# Lamp_Logic_Board_3.net
KiCad netlist of a schematic drawn in EAGLE
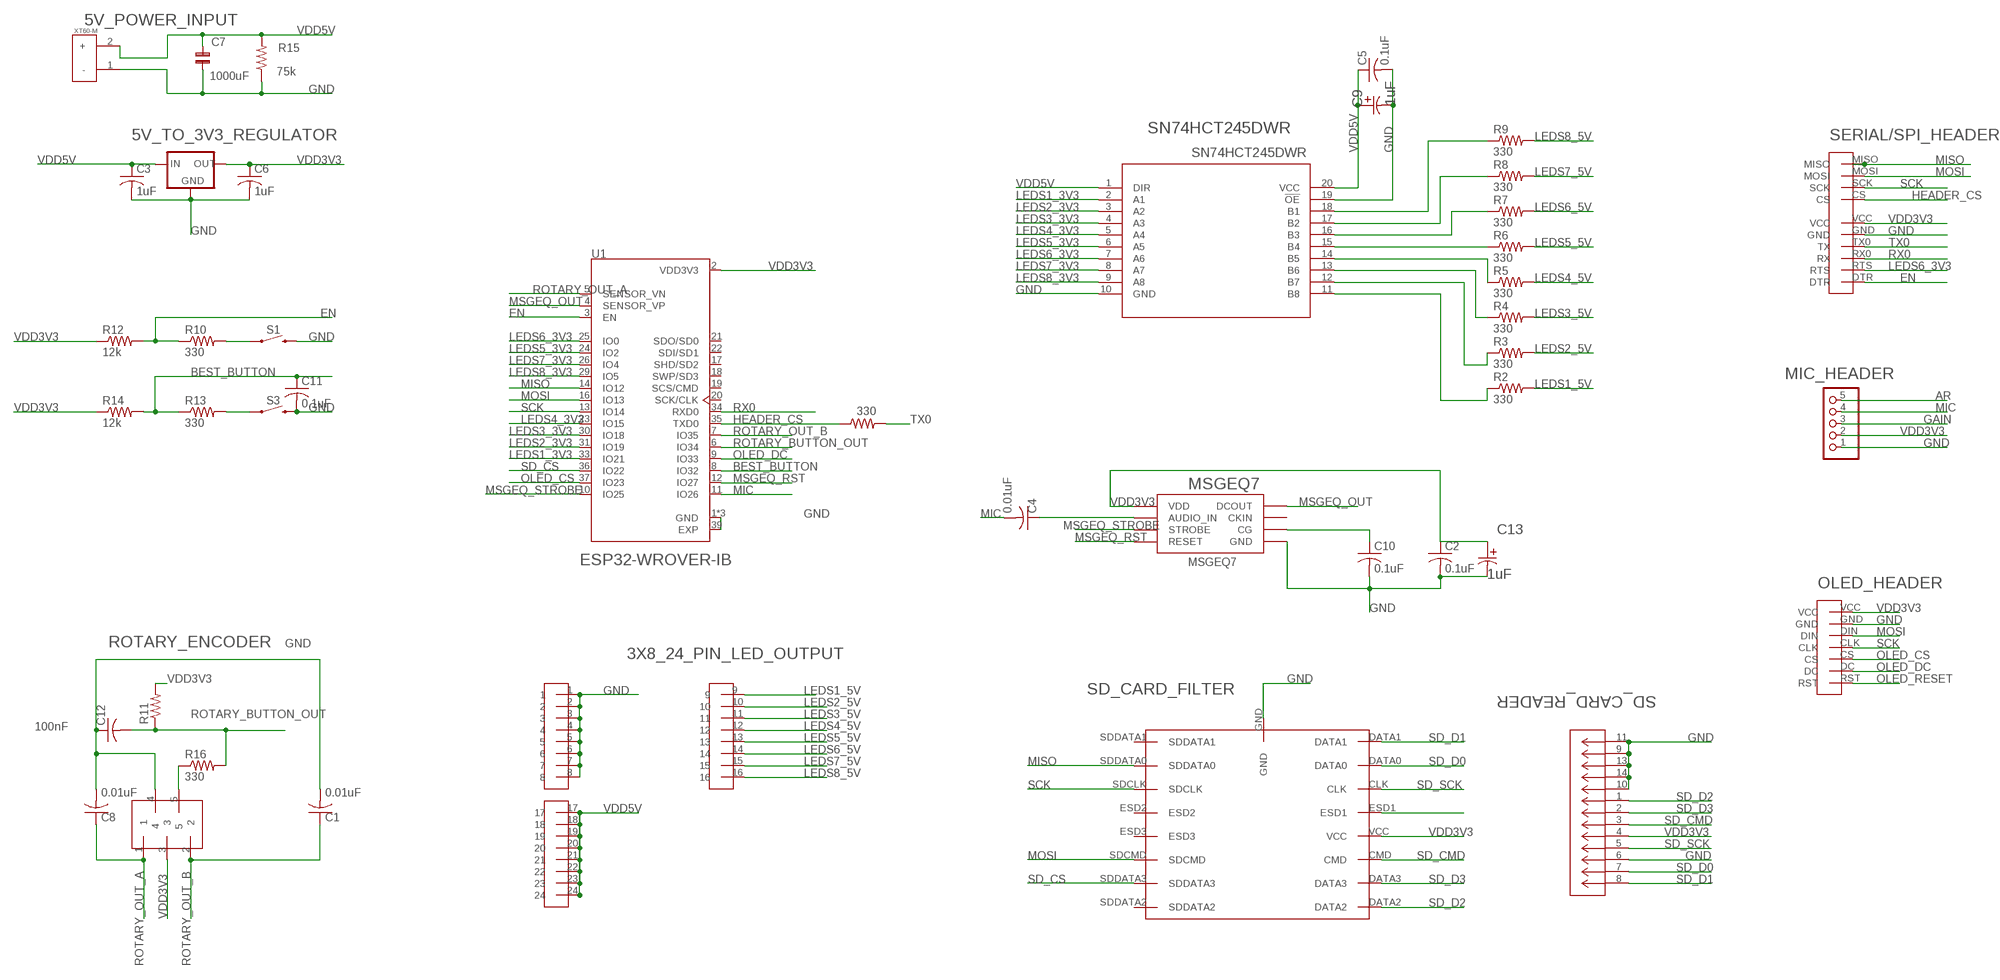
[diagram p0: schematic, sheet 1]

(export (version "E")
  (design (tool "Eeschema 10.0.6"))
  (components
    (comp (ref "3X8_24_PIN_LED_OUTPUT")
      (value "3X8PINHEAD")
      (footprint "eagle-import:3X8PINHEAD")
      (libsource (lib "eagle-import") (part "3X8PINHEAD"))
    )
    (comp (ref "5V_POWER_INPUT")
      (value "XT60-M")
      (footprint "eagle-import:AMASS_XT60-M")
      (fields (field (name "MF") "AMASS"))
      (libsource (lib "eagle-import") (part "XT60-M"))
    )
    (comp (ref "5V_TO_3V3_REGULATOR")
      (value "LM1117MP-1.8")
      (footprint "eagle-import:SOT223")
      (fields (field (name "MF") "Texas Instruments"))
      (libsource (lib "eagle-import") (part "LM1117?-MP1.8"))
    )
    (comp (ref "C1")
      (value "0.01uF")
      (footprint "eagle-import:C0402")
      (libsource (lib "eagle-import") (part "C-USC0402"))
    )
    (comp (ref "C2")
      (value "0.1uF")
      (footprint "eagle-import:C0805")
      (libsource (lib "eagle-import") (part "C-USC0805"))
    )
    (comp (ref "C3")
      (value "1uF")
      (footprint "eagle-import:C0402")
      (libsource (lib "eagle-import") (part "C-USC0402"))
    )
    (comp (ref "C4")
      (value "0.01uF")
      (footprint "eagle-import:C0402")
      (libsource (lib "eagle-import") (part "C-USC0402"))
    )
    (comp (ref "C5")
      (value "0.1uF")
      (footprint "eagle-import:C0805")
      (libsource (lib "eagle-import") (part "C-USC0805"))
    )
    (comp (ref "C6")
      (value "1uF")
      (footprint "eagle-import:C0402")
      (libsource (lib "eagle-import") (part "C-USC0402"))
    )
    (comp (ref "C7")
      (value "1000uF")
      (footprint "eagle-import:ENP2,0-5")
      (libsource (lib "eagle-import") (part "C-BP-2,0X5"))
    )
    (comp (ref "C8")
      (value "0.01uF")
      (footprint "eagle-import:C0402")
      (libsource (lib "eagle-import") (part "C-USC0402"))
    )
    (comp (ref "C9")
      (value "1uF")
      (footprint "eagle-import:CAP_EEFC_B")
      (fields (field (name "MANUFACTURER_PART_NUMBER") "EEEFC1V1R0R"))
      (libsource (lib "eagle-import") (part "EEEFC1V1R0R"))
    )
    (comp (ref "C10")
      (value "0.1uF")
      (footprint "eagle-import:C0805")
      (libsource (lib "eagle-import") (part "C-USC0805"))
    )
    (comp (ref "C11")
      (value "0.1uF")
      (footprint "eagle-import:C0805")
      (libsource (lib "eagle-import") (part "C-USC0805"))
    )
    (comp (ref "C12")
      (value "100nF")
      (footprint "eagle-import:C0402")
      (libsource (lib "eagle-import") (part "C-USC0402"))
    )
    (comp (ref "C13")
      (value "1uF")
      (footprint "eagle-import:CAP_EEFC_B")
      (fields (field (name "MANUFACTURER_PART_NUMBER") "EEEFC1V1R0R"))
      (libsource (lib "eagle-import") (part "EEEFC1V1R0R"))
    )
    (comp (ref "MIC_HEADER")
      (value "PINHD-1X5")
      (footprint "eagle-import:1X05")
      (libsource (lib "eagle-import") (part "PINHD-1X5"))
    )
    (comp (ref "MSGEQ7")
      (value "MSGEQ7DIL")
      (footprint "eagle-import:DIL-08")
      (fields
        (field (name "DIGI-KEY_PART_NUMBER") "1568-1544-ND")
        (field (name "MF") "SparkFun Electronics")
        (field (name "MP") "MSGEQ7")
      )
      (libsource (lib "eagle-import") (part "MSGEQ7DIL"))
    )
    (comp (ref "OLED_HEADER")
      (value "SPIOLED_STANDOFF")
      (footprint "eagle-import:SPIOLED_STADOFF")
      (libsource (lib "eagle-import") (part "SPIOLED_STANDOFF"))
    )
    (comp (ref "R1")
      (value "330")
      (footprint "eagle-import:R1206")
      (libsource (lib "eagle-import") (part "R-US_R1206"))
    )
    (comp (ref "R2")
      (value "330")
      (footprint "eagle-import:R1206")
      (libsource (lib "eagle-import") (part "R-US_R1206"))
    )
    (comp (ref "R3")
      (value "330")
      (footprint "eagle-import:R1206")
      (libsource (lib "eagle-import") (part "R-US_R1206"))
    )
    (comp (ref "R4")
      (value "330")
      (footprint "eagle-import:R1206")
      (libsource (lib "eagle-import") (part "R-US_R1206"))
    )
    (comp (ref "R5")
      (value "330")
      (footprint "eagle-import:R1206")
      (libsource (lib "eagle-import") (part "R-US_R1206"))
    )
    (comp (ref "R6")
      (value "330")
      (footprint "eagle-import:R1206")
      (libsource (lib "eagle-import") (part "R-US_R1206"))
    )
    (comp (ref "R7")
      (value "330")
      (footprint "eagle-import:R1206")
      (libsource (lib "eagle-import") (part "R-US_R1206"))
    )
    (comp (ref "R8")
      (value "330")
      (footprint "eagle-import:R1206")
      (libsource (lib "eagle-import") (part "R-US_R1206"))
    )
    (comp (ref "R9")
      (value "330")
      (footprint "eagle-import:R1206")
      (libsource (lib "eagle-import") (part "R-US_R1206"))
    )
    (comp (ref "R10")
      (value "330")
      (footprint "eagle-import:R1206")
      (libsource (lib "eagle-import") (part "R-US_R1206"))
    )
    (comp (ref "R11")
      (value "R-US_R0603")
      (footprint "eagle-import:R0603")
      (libsource (lib "eagle-import") (part "R-US_R0603"))
    )
    (comp (ref "R12")
      (value "12k")
      (footprint "eagle-import:R0603")
      (libsource (lib "eagle-import") (part "R-US_R0603"))
    )
    (comp (ref "R13")
      (value "330")
      (footprint "eagle-import:R1206")
      (libsource (lib "eagle-import") (part "R-US_R1206"))
    )
    (comp (ref "R14")
      (value "12k")
      (footprint "eagle-import:R0603")
      (libsource (lib "eagle-import") (part "R-US_R0603"))
    )
    (comp (ref "R15")
      (value "75k")
      (footprint "eagle-import:0309_12")
      (libsource (lib "eagle-import") (part "R-US_0309/12"))
    )
    (comp (ref "R16")
      (value "330")
      (footprint "eagle-import:R1206")
      (libsource (lib "eagle-import") (part "R-US_R1206"))
    )
    (comp (ref "ROTARY_ENCODER")
      (value "EN11-HSM1AF15")
      (footprint "eagle-import:EN11-HSM")
      (libsource (lib "eagle-import") (part "EN11-HSM1AF15"))
    )
    (comp (ref "S1")
      (value "MOMENTARY-SWITCH-SPST-SMD-6.0X3.5MM")
      (footprint "eagle-import:TACTILE_SWITCH_SMD_6.0X3.5MM")
      (libsource (lib "eagle-import") (part "MOMENTARY-SWITCH-SPST-SMD-6.0X3.5MM"))
    )
    (comp (ref "S3")
      (value "MOMENTARY-SWITCH-SPST-SMD-12MM")
      (footprint "eagle-import:TACTILE_SWITCH_SMD_12MM")
      (libsource (lib "eagle-import") (part "MOMENTARY-SWITCH-SPST-SMD-12MM"))
    )
    (comp (ref "SD_CARD_FILTER")
      (value "CM1624-08DE")
      (footprint "eagle-import:CM1624-08DE")
      (libsource (lib "eagle-import") (part "CM1624-08DE"))
    )
    (comp (ref "SD_CARD_READER")
      (value "LLC")
      (footprint "eagle-import:CON00218_8")
      (libsource (lib "eagle-import") (part "LLC"))
    )
    (comp (ref "SERIAL/SPI_HEADER")
      (value "2X6PINHEAD")
      (footprint "eagle-import:2X6PINHEAD")
      (libsource (lib "eagle-import") (part "2X6PINHEAD"))
    )
    (comp (ref "SN74HCT245DWR")
      (value "SN74HCT245DWR")
      (footprint "eagle-import:DW20")
      (libsource (lib "eagle-import") (part "SN74HCT245DWR"))
    )
    (comp (ref "U1")
      (value "ESP32-WROVER-IB")
      (footprint "eagle-import:XCVR_ESP32-WROVER-I")
      (fields (field (name "MF") "Espressif Systems") (field (name "MP") "ESP32-WROVER-I"))
      (libsource (lib "eagle-import") (part "ESP32-WROVER-I"))
    )
  )
  (nets
    (net (code "1") (name "AR") (class "Default")
      (node (ref "MIC_HEADER") (pin "5") (pinfunction "5_5") (pintype "passive"))
    )
    (net (code "2") (name "BEST_BUTTON") (class "Default")
      (node (ref "C11") (pin "1") (pinfunction "1_1") (pintype "passive"))
      (node (ref "R13") (pin "1") (pinfunction "1_1") (pintype "passive"))
      (node (ref "R14") (pin "2") (pinfunction "2_2") (pintype "passive"))
      (node (ref "U1") (pin "8") (pinfunction "IO32_8") (pintype "bidirectional"))
    )
    (net (code "3") (name "EN") (class "Default")
      (node (ref "R10") (pin "1") (pinfunction "1_1") (pintype "passive"))
      (node (ref "R12") (pin "2") (pinfunction "2_2") (pintype "passive"))
      (node (ref "SERIAL/SPI_HEADER") (pin "DTR") (pinfunction "DTR_DTR") (pintype "bidirectional"))
      (node (ref "U1") (pin "3") (pinfunction "EN_3") (pintype "input"))
    )
    (net (code "4") (name "GAIN") (class "Default")
      (node (ref "MIC_HEADER") (pin "3") (pinfunction "3_3") (pintype "passive"))
    )
    (net (code "5") (name "GND") (class "Default")
      (node (ref "3X8_24_PIN_LED_OUTPUT") (pin "1") (pinfunction "1_1") (pintype "bidirectional"))
      (node (ref "3X8_24_PIN_LED_OUTPUT") (pin "2") (pinfunction "2_2") (pintype "bidirectional"))
      (node (ref "3X8_24_PIN_LED_OUTPUT") (pin "3") (pinfunction "3_3") (pintype "bidirectional"))
      (node (ref "3X8_24_PIN_LED_OUTPUT") (pin "4") (pinfunction "4_4") (pintype "bidirectional"))
      (node (ref "3X8_24_PIN_LED_OUTPUT") (pin "5") (pinfunction "5_5") (pintype "bidirectional"))
      (node (ref "3X8_24_PIN_LED_OUTPUT") (pin "6") (pinfunction "6_6") (pintype "bidirectional"))
      (node (ref "3X8_24_PIN_LED_OUTPUT") (pin "7") (pinfunction "7_7") (pintype "bidirectional"))
      (node (ref "3X8_24_PIN_LED_OUTPUT") (pin "8") (pinfunction "8_8") (pintype "bidirectional"))
      (node (ref "5V_POWER_INPUT") (pin "1") (pinfunction "-_1") (pintype "passive"))
      (node (ref "5V_TO_3V3_REGULATOR") (pin "1") (pinfunction "GND_1") (pintype "input"))
      (node (ref "C1") (pin "2") (pinfunction "2_2") (pintype "passive"))
      (node (ref "C10") (pin "2") (pinfunction "2_2") (pintype "passive"))
      (node (ref "C11") (pin "2") (pinfunction "2_2") (pintype "passive"))
      (node (ref "C12") (pin "1") (pinfunction "1_1") (pintype "passive"))
      (node (ref "C13") (pin "2") (pinfunction "2_2") (pintype "passive"))
      (node (ref "C2") (pin "2") (pinfunction "2_2") (pintype "passive"))
      (node (ref "C3") (pin "2") (pinfunction "2_2") (pintype "passive"))
      (node (ref "C5") (pin "2") (pinfunction "2_2") (pintype "passive"))
      (node (ref "C6") (pin "2") (pinfunction "2_2") (pintype "passive"))
      (node (ref "C7") (pin "1") (pinfunction "1_1") (pintype "passive"))
      (node (ref "C8") (pin "2") (pinfunction "2_2") (pintype "passive"))
      (node (ref "C9") (pin "2") (pinfunction "2_2") (pintype "passive"))
      (node (ref "MIC_HEADER") (pin "1") (pinfunction "1_1") (pintype "passive"))
      (node (ref "MSGEQ7") (pin "2") (pinfunction "GND_2") (pintype "bidirectional"))
      (node (ref "OLED_HEADER") (pin "GND") (pinfunction "GND_GND") (pintype "bidirectional"))
      (node (ref "R15") (pin "1") (pinfunction "1_1") (pintype "passive"))
      (node (ref "ROTARY_ENCODER") (pin "4") (pinfunction "4_4") (pintype "bidirectional"))
      (node (ref "S1") (pin "2") (pinfunction "2_2") (pintype "passive"))
      (node (ref "S3") (pin "3") (pinfunction "2_3") (pintype "passive"))
      (node (ref "SD_CARD_FILTER") (pin "GND") (pinfunction "GND_GND") (pintype "bidirectional"))
      (node (ref "SD_CARD_READER") (pin "10") (pinfunction "10_10") (pintype "passive"))
      (node (ref "SD_CARD_READER") (pin "11") (pinfunction "11_11") (pintype "passive"))
      (node (ref "SD_CARD_READER") (pin "13") (pinfunction "13_13") (pintype "passive"))
      (node (ref "SD_CARD_READER") (pin "14") (pinfunction "14_14") (pintype "passive"))
      (node (ref "SD_CARD_READER") (pin "6") (pinfunction "6_6") (pintype "passive"))
      (node (ref "SD_CARD_READER") (pin "9") (pinfunction "9_9") (pintype "passive"))
      (node (ref "SERIAL/SPI_HEADER") (pin "GND") (pinfunction "GND_GND") (pintype "bidirectional"))
      (node (ref "SN74HCT245DWR") (pin "10") (pinfunction "GND_10") (pintype "power_in"))
      (node (ref "SN74HCT245DWR") (pin "19") (pinfunction "~{OE}_19") (pintype "input"))
      (node (ref "U1") (pin "1") (pinfunction "GND_1") (pintype "power_in"))
      (node (ref "U1") (pin "15") (pinfunction "GND_15") (pintype "power_in"))
      (node (ref "U1") (pin "38") (pinfunction "GND_38") (pintype "power_in"))
      (node (ref "U1") (pin "39") (pinfunction "EXP_39") (pintype "power_in"))
    )
    (net (code "6") (name "HEADER_CS") (class "Default")
      (node (ref "R1") (pin "1") (pinfunction "1_1") (pintype "passive"))
      (node (ref "SERIAL/SPI_HEADER") (pin "CS") (pinfunction "CS_CS") (pintype "bidirectional"))
      (node (ref "U1") (pin "35") (pinfunction "TXD0_35") (pintype "bidirectional"))
    )
    (net (code "7") (name "LEDS1_3V3") (class "Default")
      (node (ref "SN74HCT245DWR") (pin "2") (pinfunction "A1_2") (pintype "bidirectional"))
      (node (ref "U1") (pin "33") (pinfunction "IO21_33") (pintype "bidirectional"))
    )
    (net (code "8") (name "LEDS1_5V") (class "Default")
      (node (ref "3X8_24_PIN_LED_OUTPUT") (pin "9") (pinfunction "9_9") (pintype "bidirectional"))
      (node (ref "R2") (pin "2") (pinfunction "2_2") (pintype "passive"))
    )
    (net (code "9") (name "LEDS2_3V3") (class "Default")
      (node (ref "SN74HCT245DWR") (pin "3") (pinfunction "A2_3") (pintype "bidirectional"))
      (node (ref "U1") (pin "31") (pinfunction "IO19_31") (pintype "bidirectional"))
    )
    (net (code "10") (name "LEDS2_5V") (class "Default")
      (node (ref "3X8_24_PIN_LED_OUTPUT") (pin "10") (pinfunction "10_10") (pintype "bidirectional"))
      (node (ref "R3") (pin "2") (pinfunction "2_2") (pintype "passive"))
    )
    (net (code "11") (name "LEDS3_3V3") (class "Default")
      (node (ref "SN74HCT245DWR") (pin "4") (pinfunction "A3_4") (pintype "bidirectional"))
      (node (ref "U1") (pin "30") (pinfunction "IO18_30") (pintype "bidirectional"))
    )
    (net (code "12") (name "LEDS3_5V") (class "Default")
      (node (ref "3X8_24_PIN_LED_OUTPUT") (pin "11") (pinfunction "11_11") (pintype "bidirectional"))
      (node (ref "R4") (pin "2") (pinfunction "2_2") (pintype "passive"))
    )
    (net (code "13") (name "LEDS4_3V3") (class "Default")
      (node (ref "SN74HCT245DWR") (pin "5") (pinfunction "A4_5") (pintype "bidirectional"))
      (node (ref "U1") (pin "23") (pinfunction "IO15_23") (pintype "bidirectional"))
    )
    (net (code "14") (name "LEDS4_5V") (class "Default")
      (node (ref "3X8_24_PIN_LED_OUTPUT") (pin "12") (pinfunction "12_12") (pintype "bidirectional"))
      (node (ref "R5") (pin "2") (pinfunction "2_2") (pintype "passive"))
    )
    (net (code "15") (name "LEDS5_3V3") (class "Default")
      (node (ref "SN74HCT245DWR") (pin "6") (pinfunction "A5_6") (pintype "bidirectional"))
      (node (ref "U1") (pin "24") (pinfunction "IO2_24") (pintype "bidirectional"))
    )
    (net (code "16") (name "LEDS5_5V") (class "Default")
      (node (ref "3X8_24_PIN_LED_OUTPUT") (pin "13") (pinfunction "13_13") (pintype "bidirectional"))
      (node (ref "R6") (pin "2") (pinfunction "2_2") (pintype "passive"))
    )
    (net (code "17") (name "LEDS6_3V3") (class "Default")
      (node (ref "SERIAL/SPI_HEADER") (pin "RTS") (pinfunction "RTS_RTS") (pintype "bidirectional"))
      (node (ref "SN74HCT245DWR") (pin "7") (pinfunction "A6_7") (pintype "bidirectional"))
      (node (ref "U1") (pin "25") (pinfunction "IO0_25") (pintype "bidirectional"))
    )
    (net (code "18") (name "LEDS6_5V") (class "Default")
      (node (ref "3X8_24_PIN_LED_OUTPUT") (pin "14") (pinfunction "14_14") (pintype "bidirectional"))
      (node (ref "R7") (pin "2") (pinfunction "2_2") (pintype "passive"))
    )
    (net (code "19") (name "LEDS7_3V3") (class "Default")
      (node (ref "SN74HCT245DWR") (pin "8") (pinfunction "A7_8") (pintype "bidirectional"))
      (node (ref "U1") (pin "26") (pinfunction "IO4_26") (pintype "bidirectional"))
    )
    (net (code "20") (name "LEDS7_5V") (class "Default")
      (node (ref "3X8_24_PIN_LED_OUTPUT") (pin "15") (pinfunction "15_15") (pintype "bidirectional"))
      (node (ref "R8") (pin "2") (pinfunction "2_2") (pintype "passive"))
    )
    (net (code "21") (name "LEDS8_3V3") (class "Default")
      (node (ref "SN74HCT245DWR") (pin "9") (pinfunction "A8_9") (pintype "bidirectional"))
      (node (ref "U1") (pin "29") (pinfunction "IO5_29") (pintype "bidirectional"))
    )
    (net (code "22") (name "LEDS8_5V") (class "Default")
      (node (ref "3X8_24_PIN_LED_OUTPUT") (pin "16") (pinfunction "16_16") (pintype "bidirectional"))
      (node (ref "R9") (pin "2") (pinfunction "2_2") (pintype "passive"))
    )
    (net (code "23") (name "MIC") (class "Default")
      (node (ref "C4") (pin "2") (pinfunction "2_2") (pintype "passive"))
      (node (ref "MIC_HEADER") (pin "4") (pinfunction "4_4") (pintype "passive"))
      (node (ref "U1") (pin "11") (pinfunction "IO26_11") (pintype "bidirectional"))
    )
    (net (code "24") (name "MISO") (class "Default")
      (node (ref "SD_CARD_FILTER") (pin "SDDATA0") (pinfunction "SDDATA0_SDDATA0") (pintype "bidirectional"))
      (node (ref "SERIAL/SPI_HEADER") (pin "MISO") (pinfunction "MISO_MISO") (pintype "bidirectional"))
      (node (ref "U1") (pin "14") (pinfunction "IO12_14") (pintype "bidirectional"))
    )
    (net (code "25") (name "MOSI") (class "Default")
      (node (ref "OLED_HEADER") (pin "DIN") (pinfunction "DIN_DIN") (pintype "bidirectional"))
      (node (ref "SD_CARD_FILTER") (pin "SDCMD") (pinfunction "SDCMD_SDCMD") (pintype "bidirectional"))
      (node (ref "SERIAL/SPI_HEADER") (pin "MOSI") (pinfunction "MOSI_MOSI") (pintype "bidirectional"))
      (node (ref "U1") (pin "16") (pinfunction "IO13_16") (pintype "bidirectional"))
    )
    (net (code "26") (name "MSGEQ_OUT") (class "Default")
      (node (ref "MSGEQ7") (pin "3") (pinfunction "DCOUT_3") (pintype "bidirectional"))
      (node (ref "U1") (pin "4") (pinfunction "SENSOR_VP_4") (pintype "input"))
    )
    (net (code "27") (name "MSGEQ_RST") (class "Default")
      (node (ref "MSGEQ7") (pin "7") (pinfunction "RESET_7") (pintype "input"))
      (node (ref "U1") (pin "12") (pinfunction "IO27_12") (pintype "bidirectional"))
    )
    (net (code "28") (name "MSGEQ_STROBE") (class "Default")
      (node (ref "MSGEQ7") (pin "4") (pinfunction "STROBE_4") (pintype "input"))
      (node (ref "U1") (pin "10") (pinfunction "IO25_10") (pintype "bidirectional"))
    )
    (net (code "29") (name "Net-(MSGEQ7-AUDIO_IN)") (class "Default")
      (node (ref "C4") (pin "1") (pinfunction "1_1") (pintype "passive"))
      (node (ref "MSGEQ7") (pin "5") (pinfunction "AUDIO_IN_5") (pintype "input"))
    )
    (net (code "30") (name "Net-(MSGEQ7-CG)") (class "Default")
      (node (ref "C10") (pin "1") (pinfunction "1_1") (pintype "passive"))
      (node (ref "MSGEQ7") (pin "6") (pinfunction "CG_6") (pintype "bidirectional"))
    )
    (net (code "31") (name "Net-(R10-Pad2)") (class "Default")
      (node (ref "R10") (pin "2") (pinfunction "2_2") (pintype "passive"))
      (node (ref "S1") (pin "1") (pinfunction "1_1") (pintype "passive"))
    )
    (net (code "32") (name "Net-(R13-Pad2)") (class "Default")
      (node (ref "R13") (pin "2") (pinfunction "2_2") (pintype "passive"))
      (node (ref "S3") (pin "1") (pinfunction "1_1") (pintype "passive"))
    )
    (net (code "33") (name "Net-(R16-Pad1)") (class "Default")
      (node (ref "R16") (pin "1") (pinfunction "1_1") (pintype "passive"))
      (node (ref "ROTARY_ENCODER") (pin "5") (pinfunction "5_5") (pintype "bidirectional"))
    )
    (net (code "34") (name "Net-(SN74HCT245DWR-B1)") (class "Default")
      (node (ref "R9") (pin "1") (pinfunction "1_1") (pintype "passive"))
      (node (ref "SN74HCT245DWR") (pin "18") (pinfunction "B1_18") (pintype "bidirectional"))
    )
    (net (code "35") (name "Net-(SN74HCT245DWR-B2)") (class "Default")
      (node (ref "R8") (pin "1") (pinfunction "1_1") (pintype "passive"))
      (node (ref "SN74HCT245DWR") (pin "17") (pinfunction "B2_17") (pintype "bidirectional"))
    )
    (net (code "36") (name "Net-(SN74HCT245DWR-B3)") (class "Default")
      (node (ref "R7") (pin "1") (pinfunction "1_1") (pintype "passive"))
      (node (ref "SN74HCT245DWR") (pin "16") (pinfunction "B3_16") (pintype "bidirectional"))
    )
    (net (code "37") (name "Net-(SN74HCT245DWR-B4)") (class "Default")
      (node (ref "R6") (pin "1") (pinfunction "1_1") (pintype "passive"))
      (node (ref "SN74HCT245DWR") (pin "15") (pinfunction "B4_15") (pintype "bidirectional"))
    )
    (net (code "38") (name "Net-(SN74HCT245DWR-B5)") (class "Default")
      (node (ref "R5") (pin "1") (pinfunction "1_1") (pintype "passive"))
      (node (ref "SN74HCT245DWR") (pin "14") (pinfunction "B5_14") (pintype "bidirectional"))
    )
    (net (code "39") (name "Net-(SN74HCT245DWR-B6)") (class "Default")
      (node (ref "R4") (pin "1") (pinfunction "1_1") (pintype "passive"))
      (node (ref "SN74HCT245DWR") (pin "13") (pinfunction "B6_13") (pintype "bidirectional"))
    )
    (net (code "40") (name "Net-(SN74HCT245DWR-B7)") (class "Default")
      (node (ref "R3") (pin "1") (pinfunction "1_1") (pintype "passive"))
      (node (ref "SN74HCT245DWR") (pin "12") (pinfunction "B7_12") (pintype "bidirectional"))
    )
    (net (code "41") (name "Net-(SN74HCT245DWR-B8)") (class "Default")
      (node (ref "R2") (pin "1") (pinfunction "1_1") (pintype "passive"))
      (node (ref "SN74HCT245DWR") (pin "11") (pinfunction "B8_11") (pintype "bidirectional"))
    )
    (net (code "42") (name "OLED_CS") (class "Default")
      (node (ref "OLED_HEADER") (pin "CS") (pinfunction "CS_CS") (pintype "bidirectional"))
      (node (ref "U1") (pin "37") (pinfunction "IO23_37") (pintype "bidirectional"))
    )
    (net (code "43") (name "OLED_DC") (class "Default")
      (node (ref "OLED_HEADER") (pin "DC") (pinfunction "DC_DC") (pintype "bidirectional"))
      (node (ref "U1") (pin "9") (pinfunction "IO33_9") (pintype "bidirectional"))
    )
    (net (code "44") (name "OLED_RESET") (class "Default")
      (node (ref "OLED_HEADER") (pin "RST") (pinfunction "RST_RST") (pintype "bidirectional"))
    )
    (net (code "45") (name "ROTARY_BUTTON_OUT") (class "Default")
      (node (ref "C12") (pin "2") (pinfunction "2_2") (pintype "passive"))
      (node (ref "R11") (pin "1") (pinfunction "1_1") (pintype "passive"))
      (node (ref "R16") (pin "2") (pinfunction "2_2") (pintype "passive"))
      (node (ref "U1") (pin "6") (pinfunction "IO34_6") (pintype "input"))
    )
    (net (code "46") (name "ROTARY_OUT_A") (class "Default")
      (node (ref "C8") (pin "1") (pinfunction "1_1") (pintype "passive"))
      (node (ref "ROTARY_ENCODER") (pin "1") (pinfunction "1_1") (pintype "passive"))
      (node (ref "U1") (pin "5") (pinfunction "SENSOR_VN_5") (pintype "input"))
    )
    (net (code "47") (name "ROTARY_OUT_B") (class "Default")
      (node (ref "C1") (pin "1") (pinfunction "1_1") (pintype "passive"))
      (node (ref "ROTARY_ENCODER") (pin "2") (pinfunction "2_2") (pintype "passive"))
      (node (ref "U1") (pin "7") (pinfunction "IO35_7") (pintype "input"))
    )
    (net (code "48") (name "RX0") (class "Default")
      (node (ref "SERIAL/SPI_HEADER") (pin "RX0") (pinfunction "RX_RX0") (pintype "bidirectional"))
      (node (ref "U1") (pin "34") (pinfunction "RXD0_34") (pintype "bidirectional"))
    )
    (net (code "49") (name "SCK") (class "Default")
      (node (ref "OLED_HEADER") (pin "CLK") (pinfunction "CLK_CLK") (pintype "bidirectional"))
      (node (ref "SD_CARD_FILTER") (pin "SDCLK") (pinfunction "SDCLK_SDCLK") (pintype "bidirectional"))
      (node (ref "SERIAL/SPI_HEADER") (pin "SCK") (pinfunction "SCK_SCK") (pintype "bidirectional"))
      (node (ref "U1") (pin "13") (pinfunction "IO14_13") (pintype "bidirectional"))
    )
    (net (code "50") (name "SD_CMD") (class "Default")
      (node (ref "SD_CARD_FILTER") (pin "CMD") (pinfunction "CMD_CMD") (pintype "bidirectional"))
      (node (ref "SD_CARD_READER") (pin "3") (pinfunction "3_3") (pintype "passive"))
    )
    (net (code "51") (name "SD_CS") (class "Default")
      (node (ref "SD_CARD_FILTER") (pin "SDDATA3") (pinfunction "SDDATA3_SDDATA3") (pintype "bidirectional"))
      (node (ref "U1") (pin "36") (pinfunction "IO22_36") (pintype "bidirectional"))
    )
    (net (code "52") (name "SD_D0") (class "Default")
      (node (ref "SD_CARD_FILTER") (pin "DATA0") (pinfunction "DATA0_DATA0") (pintype "bidirectional"))
      (node (ref "SD_CARD_READER") (pin "7") (pinfunction "7_7") (pintype "passive"))
    )
    (net (code "53") (name "SD_D1") (class "Default")
      (node (ref "SD_CARD_FILTER") (pin "DATA1") (pinfunction "DATA1_DATA1") (pintype "bidirectional"))
      (node (ref "SD_CARD_READER") (pin "8") (pinfunction "8_8") (pintype "passive"))
    )
    (net (code "54") (name "SD_D2") (class "Default")
      (node (ref "SD_CARD_FILTER") (pin "DATA2") (pinfunction "DATA2_DATA2") (pintype "bidirectional"))
      (node (ref "SD_CARD_READER") (pin "1") (pinfunction "1_1") (pintype "passive"))
    )
    (net (code "55") (name "SD_D3") (class "Default")
      (node (ref "SD_CARD_FILTER") (pin "DATA3") (pinfunction "DATA3_DATA3") (pintype "bidirectional"))
      (node (ref "SD_CARD_READER") (pin "2") (pinfunction "2_2") (pintype "passive"))
    )
    (net (code "56") (name "SD_SCK") (class "Default")
      (node (ref "SD_CARD_FILTER") (pin "CLK") (pinfunction "CLK_CLK") (pintype "bidirectional"))
      (node (ref "SD_CARD_READER") (pin "5") (pinfunction "5_5") (pintype "passive"))
    )
    (net (code "57") (name "TX0") (class "Default")
      (node (ref "R1") (pin "2") (pinfunction "2_2") (pintype "passive"))
      (node (ref "SERIAL/SPI_HEADER") (pin "TX0") (pinfunction "TX_TX0") (pintype "bidirectional"))
    )
    (net (code "58") (name "VDD3V3") (class "Default")
      (node (ref "5V_TO_3V3_REGULATOR") (pin "2") (pinfunction "OUT_2") (pintype "passive"))
      (node (ref "5V_TO_3V3_REGULATOR") (pin "4") (pinfunction "OUT_4") (pintype "passive"))
      (node (ref "C13") (pin "1") (pinfunction "1_1") (pintype "passive"))
      (node (ref "C2") (pin "1") (pinfunction "1_1") (pintype "passive"))
      (node (ref "C6") (pin "1") (pinfunction "1_1") (pintype "passive"))
      (node (ref "MIC_HEADER") (pin "2") (pinfunction "2_2") (pintype "passive"))
      (node (ref "MSGEQ7") (pin "1") (pinfunction "VDD_1") (pintype "input"))
      (node (ref "OLED_HEADER") (pin "VCC") (pinfunction "VCC_VCC") (pintype "bidirectional"))
      (node (ref "R11") (pin "2") (pinfunction "2_2") (pintype "passive"))
      (node (ref "R12") (pin "1") (pinfunction "1_1") (pintype "passive"))
      (node (ref "R14") (pin "1") (pinfunction "1_1") (pintype "passive"))
      (node (ref "ROTARY_ENCODER") (pin "3") (pinfunction "3_3") (pintype "passive"))
      (node (ref "SD_CARD_FILTER") (pin "VCC") (pinfunction "VCC_VCC") (pintype "bidirectional"))
      (node (ref "SD_CARD_READER") (pin "4") (pinfunction "4_4") (pintype "passive"))
      (node (ref "SERIAL/SPI_HEADER") (pin "VCC") (pinfunction "VCC_VCC") (pintype "bidirectional"))
      (node (ref "U1") (pin "2") (pinfunction "VDD3V3_2") (pintype "power_in"))
    )
    (net (code "59") (name "VDD5V") (class "Default")
      (node (ref "3X8_24_PIN_LED_OUTPUT") (pin "17") (pinfunction "17_17") (pintype "bidirectional"))
      (node (ref "3X8_24_PIN_LED_OUTPUT") (pin "18") (pinfunction "18_18") (pintype "bidirectional"))
      (node (ref "3X8_24_PIN_LED_OUTPUT") (pin "19") (pinfunction "19_19") (pintype "bidirectional"))
      (node (ref "3X8_24_PIN_LED_OUTPUT") (pin "20") (pinfunction "20_20") (pintype "bidirectional"))
      (node (ref "3X8_24_PIN_LED_OUTPUT") (pin "21") (pinfunction "21_21") (pintype "bidirectional"))
      (node (ref "3X8_24_PIN_LED_OUTPUT") (pin "22") (pinfunction "22_22") (pintype "bidirectional"))
      (node (ref "3X8_24_PIN_LED_OUTPUT") (pin "23") (pinfunction "23_23") (pintype "bidirectional"))
      (node (ref "3X8_24_PIN_LED_OUTPUT") (pin "24") (pinfunction "24_24") (pintype "bidirectional"))
      (node (ref "5V_POWER_INPUT") (pin "2") (pinfunction "+_2") (pintype "passive"))
      (node (ref "5V_TO_3V3_REGULATOR") (pin "3") (pinfunction "IN_3") (pintype "input"))
      (node (ref "C3") (pin "1") (pinfunction "1_1") (pintype "passive"))
      (node (ref "C5") (pin "1") (pinfunction "1_1") (pintype "passive"))
      (node (ref "C7") (pin "2") (pinfunction "2_2") (pintype "passive"))
      (node (ref "C9") (pin "1") (pinfunction "1_1") (pintype "passive"))
      (node (ref "R15") (pin "2") (pinfunction "2_2") (pintype "passive"))
      (node (ref "SN74HCT245DWR") (pin "1") (pinfunction "DIR_1") (pintype "input"))
      (node (ref "SN74HCT245DWR") (pin "20") (pinfunction "VCC_20") (pintype "power_in"))
    )
    (net (code "60") (name "unconnected-(MSGEQ7-CKIN-Pad8)") (class "Default")
      (node (ref "MSGEQ7") (pin "8") (pinfunction "CKIN_8") (pintype "bidirectional"))
    )
    (net (code "61") (name "unconnected-(SD_CARD_FILTER-PadESD1)") (class "Default")
      (node (ref "SD_CARD_FILTER") (pin "ESD1") (pinfunction "ESD1_ESD1") (pintype "bidirectional"))
    )
    (net (code "62") (name "unconnected-(SD_CARD_FILTER-PadESD2)") (class "Default")
      (node (ref "SD_CARD_FILTER") (pin "ESD2") (pinfunction "ESD2_ESD2") (pintype "bidirectional"))
    )
    (net (code "63") (name "unconnected-(SD_CARD_FILTER-PadESD3)") (class "Default")
      (node (ref "SD_CARD_FILTER") (pin "ESD3") (pinfunction "ESD3_ESD3") (pintype "bidirectional"))
    )
    (net (code "64") (name "unconnected-(SD_CARD_FILTER-PadSDDATA1)") (class "Default")
      (node (ref "SD_CARD_FILTER") (pin "SDDATA1") (pinfunction "SDDATA1_SDDATA1") (pintype "bidirectional"))
    )
    (net (code "65") (name "unconnected-(SD_CARD_FILTER-PadSDDATA2)") (class "Default")
      (node (ref "SD_CARD_FILTER") (pin "SDDATA2") (pinfunction "SDDATA2_SDDATA2") (pintype "bidirectional"))
    )
    (net (code "66") (name "unconnected-(U1-SCK{slash}CLK-Pad20)") (class "Default")
      (node (ref "U1") (pin "20") (pinfunction "SCK/CLK_20") (pintype "bidirectional"))
    )
    (net (code "67") (name "unconnected-(U1-SCS{slash}CMD-Pad19)") (class "Default")
      (node (ref "U1") (pin "19") (pinfunction "SCS/CMD_19") (pintype "bidirectional"))
    )
    (net (code "68") (name "unconnected-(U1-SDI{slash}SD1-Pad22)") (class "Default")
      (node (ref "U1") (pin "22") (pinfunction "SDI/SD1_22") (pintype "bidirectional"))
    )
    (net (code "69") (name "unconnected-(U1-SDO{slash}SD0-Pad21)") (class "Default")
      (node (ref "U1") (pin "21") (pinfunction "SDO/SD0_21") (pintype "bidirectional"))
    )
    (net (code "70") (name "unconnected-(U1-SHD{slash}SD2-Pad17)") (class "Default")
      (node (ref "U1") (pin "17") (pinfunction "SHD/SD2_17") (pintype "bidirectional"))
    )
    (net (code "71") (name "unconnected-(U1-SWP{slash}SD3-Pad18)") (class "Default")
      (node (ref "U1") (pin "18") (pinfunction "SWP/SD3_18") (pintype "bidirectional"))
    )
  )
)
